# bluetooth.net
KiCad netlist of a schematic drawn in Altium Designer
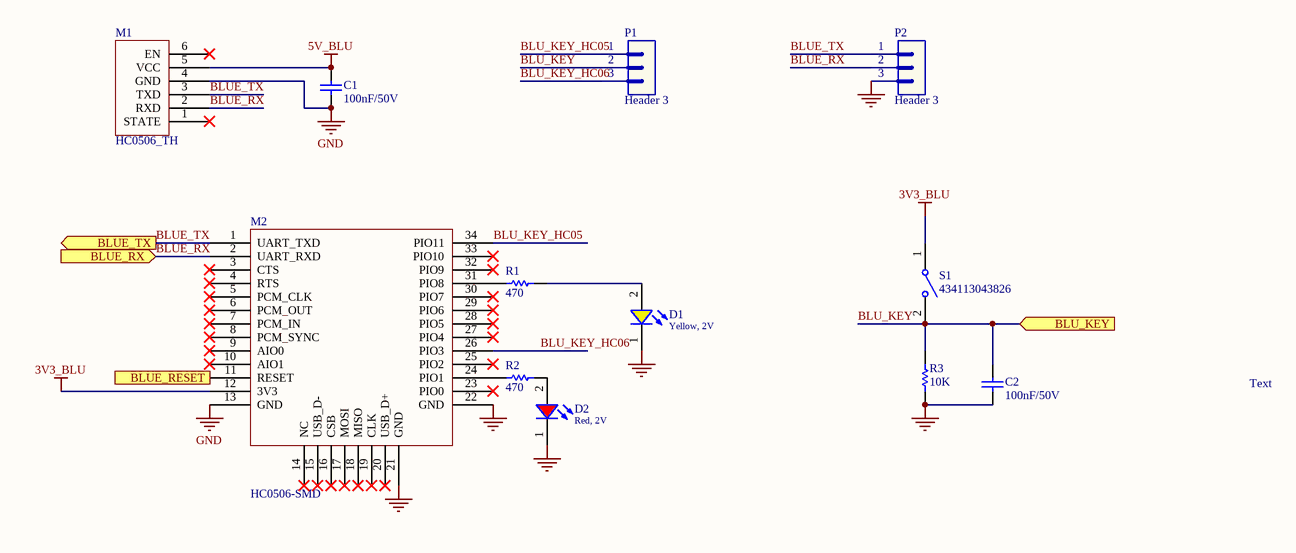
[diagram p0: bluetooth.SchDoc]

(export (version "E")
  (design (tool "Eeschema 10.0.6"))
  (components
    (comp (ref "C1")
      (value "100nF/50V")
      (footprint "CAP-SM-0805")
      (description "CAP CER 0.1UF 50V Y5V 0805")
      (fields
        (field (name "MANUFACTURER") "Samsung Electro-Mechanics")
        (field (name "MANUFACTURER PART NUMBER") "CL21F104ZBCNNNC")
      )
      (libsource (lib "Capacitor") (part "Cap-100nF-50V-0805"))
    )
    (comp (ref "C2")
      (value "100nF/50V")
      (footprint "CAP-SM-0805")
      (description "CAP CER 0.1UF 50V Y5V 0805")
      (fields
        (field (name "MANUFACTURER") "Samsung Electro-Mechanics")
        (field (name "MANUFACTURER PART NUMBER") "CL21F104ZBCNNNC")
      )
      (libsource (lib "Capacitor") (part "Cap-100nF-50V-0805"))
    )
    (comp (ref "D1")
      (value "Yellow, 2V")
      (footprint "WL-SMCW_0805")
      (description "WL-SMCW SMT Mono-color Chip LED Waterclear, size 0805, Yellow, 2V, 140deg")
      (fields (field (name "PART NUMBER") "150080YS75000") (field (name "PUBLISHER") "Wurth Elektronik"))
      (libsource (lib "150080BS75000_Altium_WL-SMCW_rev20a") (part "150080YS75000"))
    )
    (comp (ref "D2")
      (value "Red, 2V")
      (footprint "WL-SMCW_0805")
      (description "WL-SMCW SMT Mono-color Chip LED Waterclear, size 0805, Red, 2V, 140deg")
      (fields (field (name "PART NUMBER") "150080RS75000") (field (name "PUBLISHER") "Wurth Elektronik"))
      (libsource (lib "150080BS75000_Altium_WL-SMCW_rev20a") (part "150080RS75000"))
    )
    (comp (ref "M1")
      (value "HC0506_TH")
      (footprint "HC0506-TH")
      (libsource (lib "Schlib1") (part "HC0506_TH"))
    )
    (comp (ref "M2")
      (value "HC0506-SMD")
      (footprint "HC0506-SMD")
      (libsource (lib "Schlib1") (part "HC0506-SMD"))
    )
    (comp (ref "P1")
      (value "Header 3")
      (footprint "JP3")
      (description "Header, 3-Pin")
      (fields (field (name "PUBLISHER") "Altium Limited"))
      (libsource (lib "PIF_C16_2_lib") (part "Header 3"))
    )
    (comp (ref "P2")
      (value "Header 3")
      (footprint "JP3")
      (description "Header, 3-Pin")
      (fields (field (name "PUBLISHER") "Altium Limited"))
      (libsource (lib "PIF_C16_2_lib") (part "Header 3"))
    )
    (comp (ref "R1")
      (value "470")
      (footprint "Resistor:RES-SM-0805")
      (description "RES 470 OHM JUMPER 0805")
      (fields
        (field (name "MANUFACTURER") "YAG6006CT-ND")
        (field (name "MANUFACTURER PART NUMBER") "PE0805FRF7W0R047L")
      )
      (libsource (lib "Resistor") (part "Res-470-0805"))
    )
    (comp (ref "R2")
      (value "470")
      (footprint "Resistor:RES-SM-0805")
      (description "RES 470 OHM JUMPER 0805")
      (fields
        (field (name "MANUFACTURER") "YAG6006CT-ND")
        (field (name "MANUFACTURER PART NUMBER") "PE0805FRF7W0R047L")
      )
      (libsource (lib "Resistor") (part "Res-470-0805"))
    )
    (comp (ref "R3")
      (value "10K")
      (footprint "Resistor:RES-SM-0805")
      (description "RES 10K OHM 1% 1/4W 0805")
      (fields
        (field (name "MANUFACTURER") "Stackpole Electronics Inc")
        (field (name "MANUFACTURER PART NUMBER") "RNCP0805FTD10K0")
      )
      (libsource (lib "Resistor") (part "Res-10k-0805"))
    )
    (comp (ref "S1")
      (value "434113043826")
      (footprint "434113043826")
      (description "WS-TASV J-Bend SMT Tact Switch 6x3.5mm, height 4.3mm, 260gf")
      (fields (field (name "PUBLISHER") "Wurth Elektronik"))
      (libsource (lib "434113043826_Altium_WS-TASV_rev20a") (part "434113043826"))
    )
  )
  (nets
    (net (code "1") (name "/BLUE_RESET") (class "Default")
      (node (ref "M2") (pin "11") (pinfunction "RESET_11") (pintype "passive"))
    )
    (net (code "2") (name "/BLUE_RX") (class "Default")
      (node (ref "M1") (pin "2") (pinfunction "RXD_2") (pintype "passive"))
      (node (ref "M2") (pin "2") (pinfunction "UART_RXD_2") (pintype "passive"))
      (node (ref "P2") (pin "2") (pinfunction "2_2") (pintype "passive"))
    )
    (net (code "3") (name "/BLUE_TX") (class "Default")
      (node (ref "M1") (pin "3") (pinfunction "TXD_3") (pintype "passive"))
      (node (ref "M2") (pin "1") (pinfunction "UART_TXD_1") (pintype "passive"))
      (node (ref "P2") (pin "1") (pinfunction "1_1") (pintype "passive"))
    )
    (net (code "4") (name "/BLU_KEY") (class "Default")
      (node (ref "C2") (pin "2") (pinfunction "2_2") (pintype "passive"))
      (node (ref "P1") (pin "2") (pinfunction "2_2") (pintype "passive"))
      (node (ref "R3") (pin "2") (pinfunction "2_2") (pintype "passive"))
      (node (ref "S1") (pin "2") (pinfunction "2_2") (pintype "passive"))
    )
    (net (code "5") (name "/BLU_KEY_HC05") (class "Default")
      (node (ref "M2") (pin "34") (pinfunction "PIO11_34") (pintype "passive"))
      (node (ref "P1") (pin "1") (pinfunction "1_1") (pintype "passive"))
    )
    (net (code "6") (name "/BLU_KEY_HC06") (class "Default")
      (node (ref "M2") (pin "26") (pinfunction "PIO3_26") (pintype "passive"))
      (node (ref "P1") (pin "3") (pinfunction "3_3") (pintype "passive"))
    )
    (net (code "7") (name "3V3_BLU") (class "Default")
      (node (ref "M2") (pin "12") (pinfunction "3V3_12") (pintype "passive"))
      (node (ref "S1") (pin "1") (pinfunction "1_1") (pintype "passive"))
    )
    (net (code "8") (name "5V_BLU") (class "Default")
      (node (ref "C1") (pin "2") (pinfunction "2_2") (pintype "passive"))
      (node (ref "M1") (pin "5") (pinfunction "VCC_5") (pintype "passive"))
    )
    (net (code "9") (name "GND") (class "Default")
      (node (ref "C1") (pin "1") (pinfunction "1_1") (pintype "passive"))
      (node (ref "C2") (pin "1") (pinfunction "1_1") (pintype "passive"))
      (node (ref "D1") (pin "1") (pinfunction "K_1") (pintype "passive"))
      (node (ref "D2") (pin "1") (pinfunction "K_1") (pintype "passive"))
      (node (ref "M1") (pin "4") (pinfunction "GND_4") (pintype "passive"))
      (node (ref "M2") (pin "13") (pinfunction "GND_13") (pintype "passive"))
      (node (ref "M2") (pin "21") (pinfunction "GND_21") (pintype "passive"))
      (node (ref "M2") (pin "22") (pinfunction "GND_22") (pintype "passive"))
      (node (ref "P2") (pin "3") (pinfunction "3_3") (pintype "passive"))
      (node (ref "R3") (pin "1") (pinfunction "1_1") (pintype "passive"))
    )
    (net (code "10") (name "Net-(D1-A)") (class "Default")
      (node (ref "D1") (pin "2") (pinfunction "A_2") (pintype "passive"))
      (node (ref "R1") (pin "2") (pinfunction "2_2") (pintype "passive"))
    )
    (net (code "11") (name "Net-(D2-A)") (class "Default")
      (node (ref "D2") (pin "2") (pinfunction "A_2") (pintype "passive"))
      (node (ref "R2") (pin "2") (pinfunction "2_2") (pintype "passive"))
    )
    (net (code "12") (name "Net-(M2-PIO1)") (class "Default")
      (node (ref "M2") (pin "24") (pinfunction "PIO1_24") (pintype "passive"))
      (node (ref "R2") (pin "1") (pinfunction "1_1") (pintype "passive"))
    )
    (net (code "13") (name "Net-(M2-PIO8)") (class "Default")
      (node (ref "M2") (pin "31") (pinfunction "PIO8_31") (pintype "passive"))
      (node (ref "R1") (pin "1") (pinfunction "1_1") (pintype "passive"))
    )
    (net (code "14") (name "unconnected-(M1-EN-Pad6)") (class "Default")
      (node (ref "M1") (pin "6") (pinfunction "EN_6") (pintype "passive+no_connect"))
    )
    (net (code "15") (name "unconnected-(M1-STATE-Pad1)") (class "Default")
      (node (ref "M1") (pin "1") (pinfunction "STATE_1") (pintype "passive+no_connect"))
    )
    (net (code "16") (name "unconnected-(M2-AIO0-Pad9)") (class "Default")
      (node (ref "M2") (pin "9") (pinfunction "AIO0_9") (pintype "passive+no_connect"))
    )
    (net (code "17") (name "unconnected-(M2-AIO1-Pad10)") (class "Default")
      (node (ref "M2") (pin "10") (pinfunction "AIO1_10") (pintype "passive+no_connect"))
    )
    (net (code "18") (name "unconnected-(M2-CLK-Pad19)") (class "Default")
      (node (ref "M2") (pin "19") (pinfunction "CLK_19") (pintype "passive+no_connect"))
    )
    (net (code "19") (name "unconnected-(M2-CSB-Pad16)") (class "Default")
      (node (ref "M2") (pin "16") (pinfunction "CSB_16") (pintype "passive+no_connect"))
    )
    (net (code "20") (name "unconnected-(M2-CTS-Pad3)") (class "Default")
      (node (ref "M2") (pin "3") (pinfunction "CTS_3") (pintype "passive+no_connect"))
    )
    (net (code "21") (name "unconnected-(M2-MISO-Pad18)") (class "Default")
      (node (ref "M2") (pin "18") (pinfunction "MISO_18") (pintype "passive+no_connect"))
    )
    (net (code "22") (name "unconnected-(M2-MOSI-Pad17)") (class "Default")
      (node (ref "M2") (pin "17") (pinfunction "MOSI_17") (pintype "passive+no_connect"))
    )
    (net (code "23") (name "unconnected-(M2-NC-Pad14)") (class "Default")
      (node (ref "M2") (pin "14") (pinfunction "NC_14") (pintype "passive+no_connect"))
    )
    (net (code "24") (name "unconnected-(M2-PCM_CLK-Pad5)") (class "Default")
      (node (ref "M2") (pin "5") (pinfunction "PCM_CLK_5") (pintype "passive+no_connect"))
    )
    (net (code "25") (name "unconnected-(M2-PCM_IN-Pad7)") (class "Default")
      (node (ref "M2") (pin "7") (pinfunction "PCM_IN_7") (pintype "passive+no_connect"))
    )
    (net (code "26") (name "unconnected-(M2-PCM_OUT-Pad6)") (class "Default")
      (node (ref "M2") (pin "6") (pinfunction "PCM_OUT_6") (pintype "passive+no_connect"))
    )
    (net (code "27") (name "unconnected-(M2-PCM_SYNC-Pad8)") (class "Default")
      (node (ref "M2") (pin "8") (pinfunction "PCM_SYNC_8") (pintype "passive+no_connect"))
    )
    (net (code "28") (name "unconnected-(M2-PIO0-Pad23)") (class "Default")
      (node (ref "M2") (pin "23") (pinfunction "PIO0_23") (pintype "passive+no_connect"))
    )
    (net (code "29") (name "unconnected-(M2-PIO2-Pad25)") (class "Default")
      (node (ref "M2") (pin "25") (pinfunction "PIO2_25") (pintype "passive+no_connect"))
    )
    (net (code "30") (name "unconnected-(M2-PIO4-Pad27)") (class "Default")
      (node (ref "M2") (pin "27") (pinfunction "PIO4_27") (pintype "passive+no_connect"))
    )
    (net (code "31") (name "unconnected-(M2-PIO5-Pad28)") (class "Default")
      (node (ref "M2") (pin "28") (pinfunction "PIO5_28") (pintype "passive+no_connect"))
    )
    (net (code "32") (name "unconnected-(M2-PIO6-Pad29)") (class "Default")
      (node (ref "M2") (pin "29") (pinfunction "PIO6_29") (pintype "passive+no_connect"))
    )
    (net (code "33") (name "unconnected-(M2-PIO7-Pad30)") (class "Default")
      (node (ref "M2") (pin "30") (pinfunction "PIO7_30") (pintype "passive+no_connect"))
    )
    (net (code "34") (name "unconnected-(M2-PIO9-Pad32)") (class "Default")
      (node (ref "M2") (pin "32") (pinfunction "PIO9_32") (pintype "passive+no_connect"))
    )
    (net (code "35") (name "unconnected-(M2-PIO10-Pad33)") (class "Default")
      (node (ref "M2") (pin "33") (pinfunction "PIO10_33") (pintype "passive+no_connect"))
    )
    (net (code "36") (name "unconnected-(M2-RTS-Pad4)") (class "Default")
      (node (ref "M2") (pin "4") (pinfunction "RTS_4") (pintype "passive+no_connect"))
    )
    (net (code "37") (name "unconnected-(M2-USB_D+-Pad20)") (class "Default")
      (node (ref "M2") (pin "20") (pinfunction "USB_D+_20") (pintype "passive+no_connect"))
    )
    (net (code "38") (name "unconnected-(M2-USB_D--Pad15)") (class "Default")
      (node (ref "M2") (pin "15") (pinfunction "USB_D-_15") (pintype "passive+no_connect"))
    )
  )
)
